# RTC_Section.net
KiCad netlist of a schematic drawn in Altium Designer
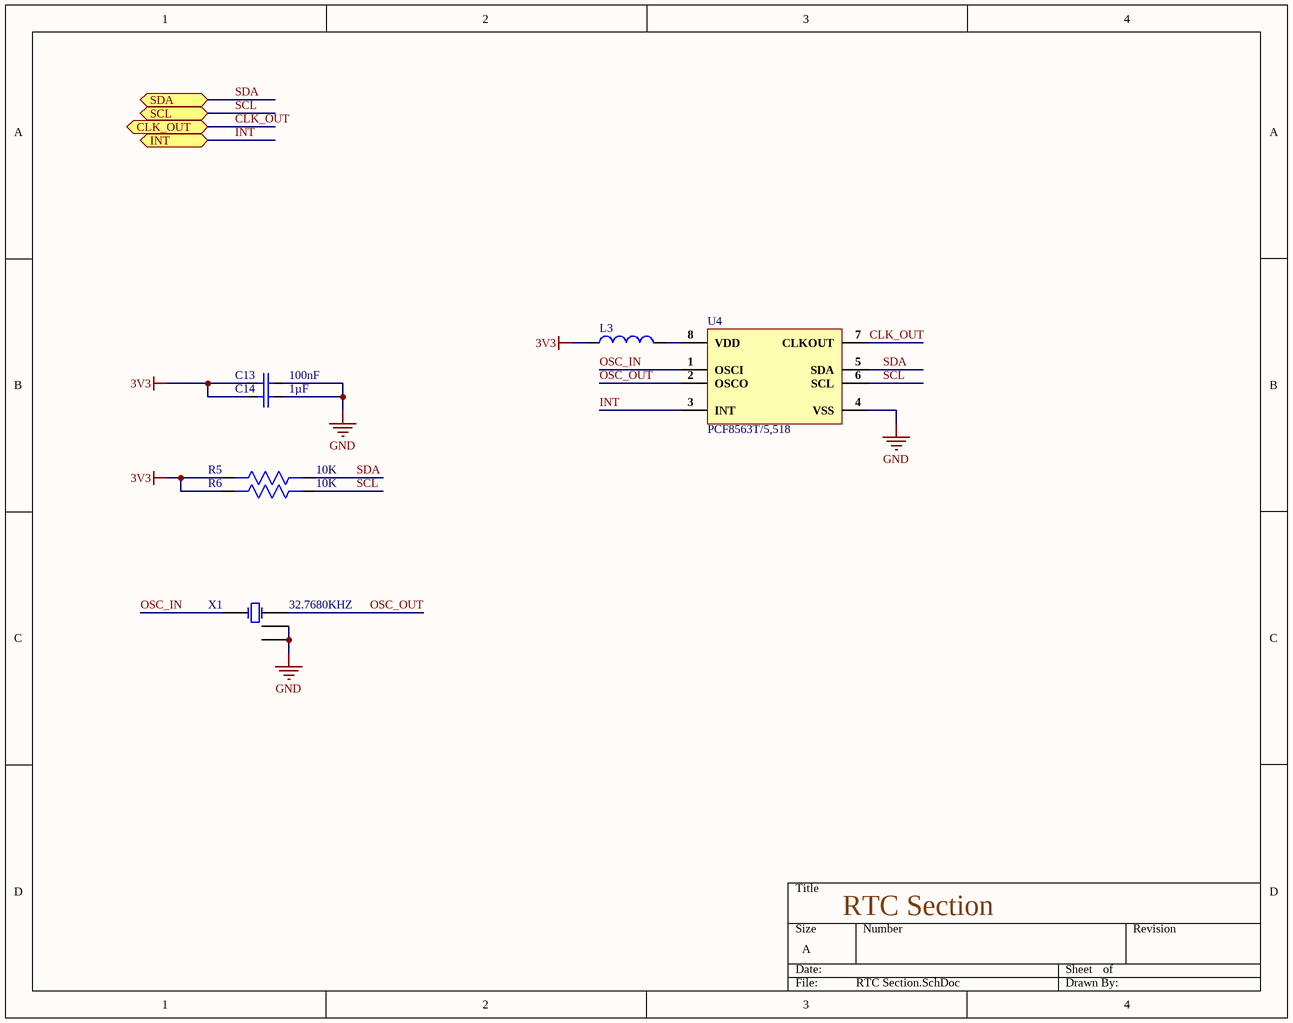
[diagram p0: RTC Section.SchDoc]

(export (version "E")
  (design (tool "Eeschema 10.0.6"))
  (components
    (comp (ref "C13")
      (value "100nF")
      (footprint "Cap0402")
      (description "Cap Ceramic 0.1uF 25V X7R 10% SMD 0402 125C Paper T/R")
      (fields
        (field (name "MANUFACTURER") "Yageo")
        (field (name "MANUFACTURER PART NUMBER") "CC0402KRX7R8BB104")
      )
      (libsource (lib "TT_IntLib") (part "CC0402KRX7R8BB104"))
    )
    (comp (ref "C14")
      (value "1µF")
      (footprint "Cap0402")
      (fields
        (field (name "MANUFACTURER") "Murata")
        (field (name "MANUFACTURER PART NUMBER") "GRM155R61E105KA12D")
        (field (name "TOLERANCE") "10%")
      )
      (libsource (lib "TT_IntLib") (part "GRM155R61E105KA12D"))
    )
    (comp (ref "L3")
      (value "MMZ0603S601CT000")
      (footprint "MMZ0603S601CT000")
      (description "FERRITE BEAD 600 OHM 0201 1LN")
      (libsource (lib "TT_IntLib") (part "MMZ0603S601CT000"))
    )
    (comp (ref "R5")
      (value "10K")
      (footprint "Res-0201")
      (description "GENERAL 0201 11% REEL (7INCH)")
      (fields
        (field (name "MANUFACTURER") "Yageo")
        (field (name "MANUFACTURER PART NUMBER") "RC0201FR-0710KL")
      )
      (libsource (lib "TT_IntLib") (part "RC0201FR-0710KL"))
    )
    (comp (ref "R6")
      (value "10K")
      (footprint "Res-0201")
      (description "GENERAL 0201 11% REEL (7INCH)")
      (fields
        (field (name "MANUFACTURER") "Yageo")
        (field (name "MANUFACTURER PART NUMBER") "RC0201FR-0710KL")
      )
      (libsource (lib "TT_IntLib") (part "RC0201FR-0710KL"))
    )
    (comp (ref "U4")
      (value "PCF8563T/5,518")
      (footprint "8-SO")
      (description "IC RTC CLK/CALENDAR I2C 8-SOIC")
      (libsource (lib "TT_IntLib") (part "PCF8563T/5,518"))
    )
    (comp (ref "X1")
      (value "32.7680KHZ")
      (footprint "CM200C32768DZFT")
      (description "CRYSTAL 32.7680KHZ 12.5PF SMD")
      (fields
        (field (name "MANUFACTURER") "Citizen")
        (field (name "MANUFACTURER PART NUMBER") "CM200C32768DZFT")
      )
      (libsource (lib "TT_IntLib") (part "CM200C32768DZFT"))
    )
  )
  (nets
    (net (code "1") (name "/CLK_OUT") (class "Default")
      (node (ref "U4") (pin "7") (pinfunction "CLKOUT_7") (pintype "passive"))
    )
    (net (code "2") (name "/INT") (class "Default")
      (node (ref "U4") (pin "3") (pinfunction "INT_3") (pintype "passive"))
    )
    (net (code "3") (name "/OSC_IN") (class "Default")
      (node (ref "U4") (pin "1") (pinfunction "OSCI_1") (pintype "passive"))
      (node (ref "X1") (pin "1") (pinfunction "OSC1_1") (pintype "passive"))
    )
    (net (code "4") (name "/OSC_OUT") (class "Default")
      (node (ref "U4") (pin "2") (pinfunction "OSCO_2") (pintype "passive"))
      (node (ref "X1") (pin "4") (pinfunction "OSC2_4") (pintype "passive"))
    )
    (net (code "5") (name "/SCL") (class "Default")
      (node (ref "R6") (pin "1") (pintype "passive"))
      (node (ref "U4") (pin "6") (pinfunction "SCL_6") (pintype "passive"))
    )
    (net (code "6") (name "/SDA") (class "Default")
      (node (ref "R5") (pin "1") (pintype "passive"))
      (node (ref "U4") (pin "5") (pinfunction "SDA_5") (pintype "passive"))
    )
    (net (code "7") (name "3V3") (class "Default")
      (node (ref "C13") (pin "2") (pintype "passive"))
      (node (ref "C14") (pin "2") (pintype "passive"))
      (node (ref "L3") (pin "1") (pinfunction "1_1") (pintype "passive"))
      (node (ref "R5") (pin "2") (pintype "passive"))
      (node (ref "R6") (pin "2") (pintype "passive"))
    )
    (net (code "8") (name "GND") (class "Default")
      (node (ref "C13") (pin "1") (pintype "passive"))
      (node (ref "C14") (pin "1") (pintype "passive"))
      (node (ref "U4") (pin "4") (pinfunction "VSS_4") (pintype "passive"))
      (node (ref "X1") (pin "2") (pinfunction "OSC3_2") (pintype "passive"))
      (node (ref "X1") (pin "3") (pinfunction "OSC4_3") (pintype "passive"))
    )
    (net (code "9") (name "Net-(U4-VDD)") (class "Default")
      (node (ref "L3") (pin "2") (pinfunction "2_2") (pintype "passive"))
      (node (ref "U4") (pin "8") (pinfunction "VDD_8") (pintype "passive"))
    )
  )
)
